# SparkFun_WiFly_GSX_Breakout.net
KiCad netlist of a schematic drawn in EAGLE
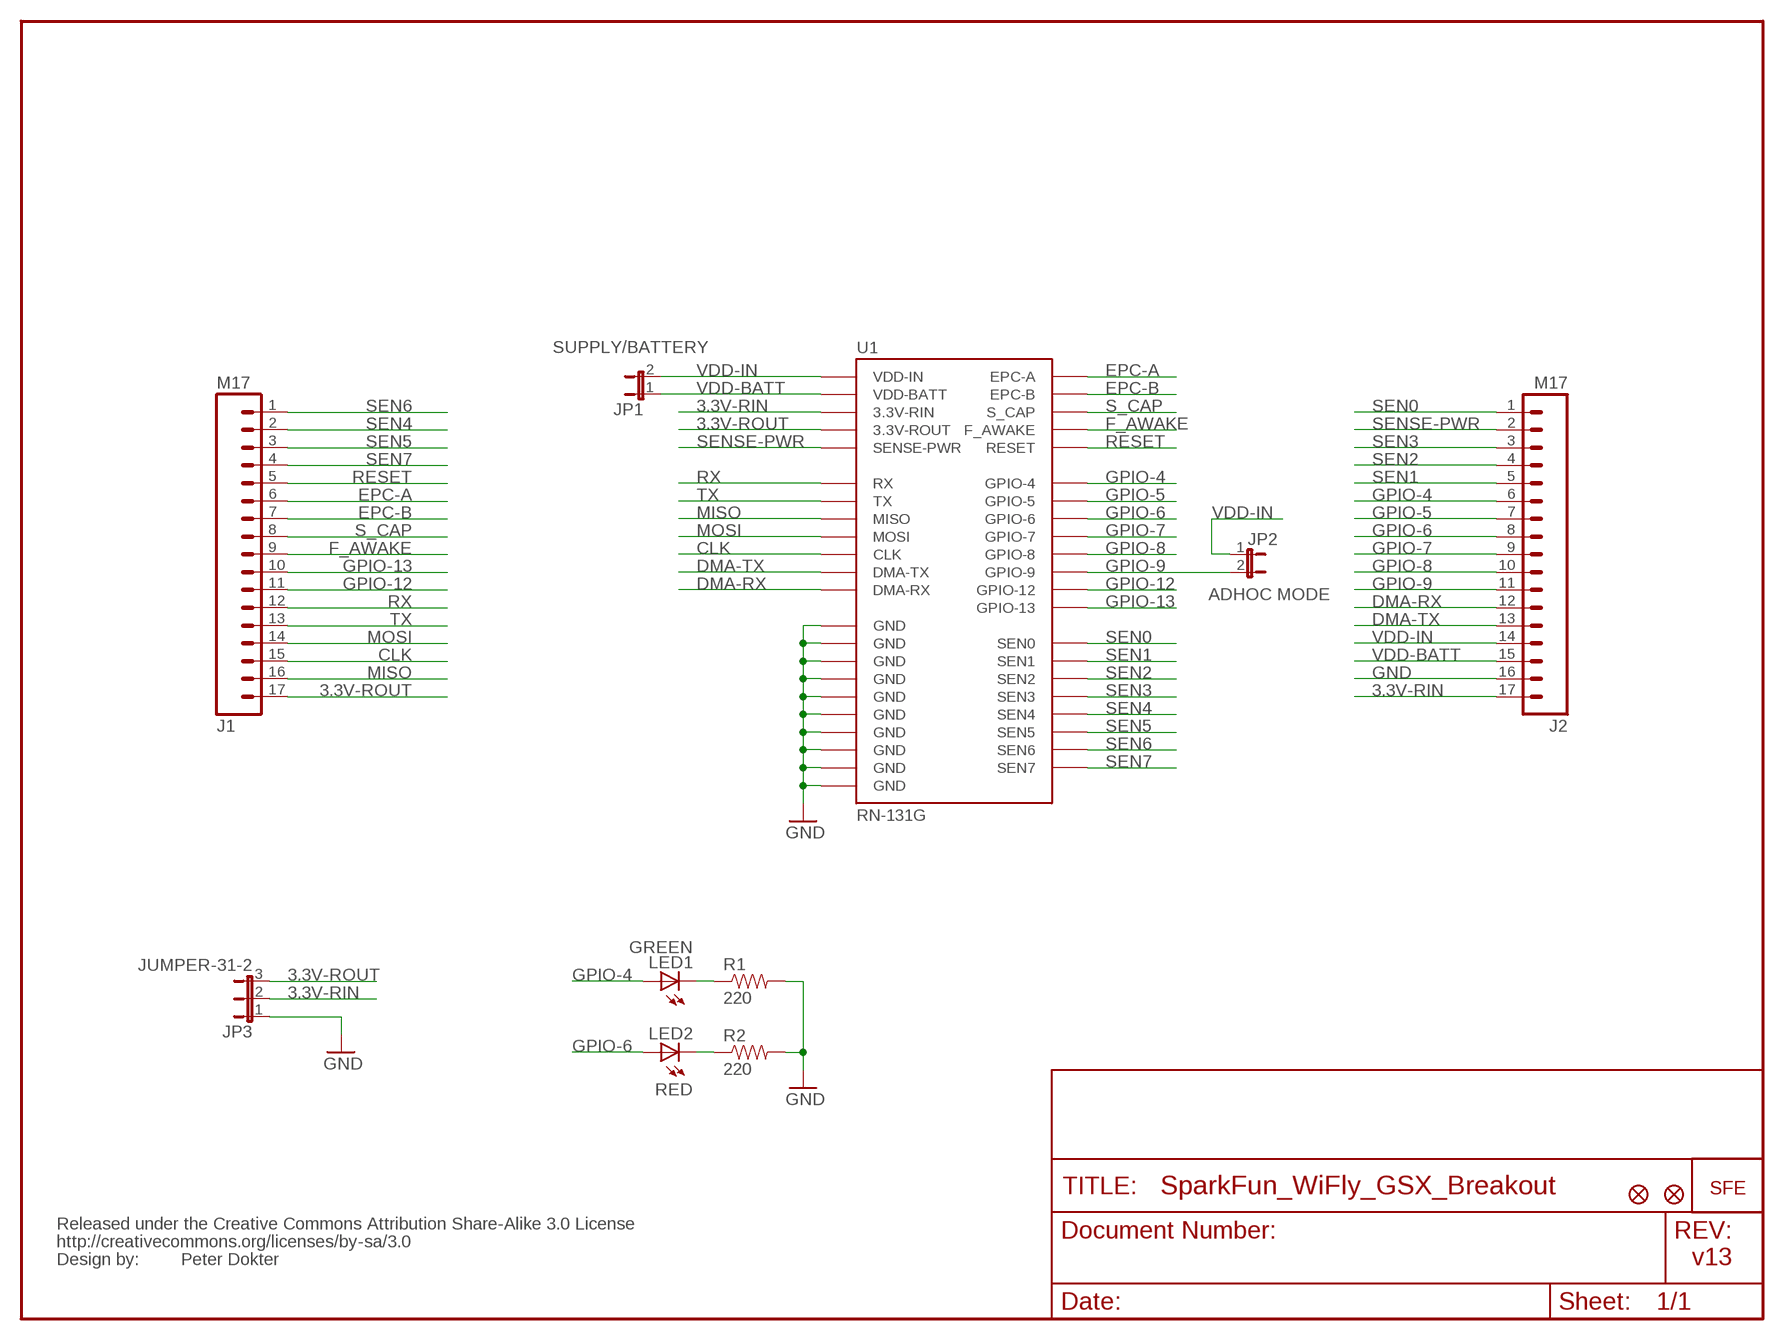
[diagram p0: schematic, sheet 1]

(export (version "E")
  (design (tool "Eeschema 10.0.6"))
  (components
    (comp (ref "J1")
      (value "M17")
      (footprint "eagle-import:1X17")
      (libsource (lib "eagle-import") (part "M17"))
    )
    (comp (ref "J2")
      (value "M17")
      (footprint "eagle-import:1X17")
      (libsource (lib "eagle-import") (part "M17"))
    )
    (comp (ref "JP1")
      (value "JUMPER-2SMD-NO")
      (footprint "eagle-import:SJ_2S-NO")
      (libsource (lib "eagle-import") (part "JUMPER-2SMD-NO"))
    )
    (comp (ref "JP2")
      (value "JUMPER-2SMD-NO")
      (footprint "eagle-import:SJ_2S-NO")
      (libsource (lib "eagle-import") (part "JUMPER-2SMD-NO"))
    )
    (comp (ref "JP3")
      (value "JUMPER-31-2")
      (footprint "eagle-import:SJ_3_PASTE1&2")
      (libsource (lib "eagle-import") (part "JUMPER-31-2"))
    )
    (comp (ref "LED1")
      (value "GREEN")
      (footprint "eagle-import:LED-0603")
      (libsource (lib "eagle-import") (part "LED0603"))
    )
    (comp (ref "LED2")
      (value "RED")
      (footprint "eagle-import:LED-0603")
      (libsource (lib "eagle-import") (part "LED0603"))
    )
    (comp (ref "R1")
      (value "220")
      (footprint "eagle-import:0402-RES")
      (libsource (lib "eagle-import") (part "RESISTOR0402-RES"))
    )
    (comp (ref "R2")
      (value "220")
      (footprint "eagle-import:0402-RES")
      (libsource (lib "eagle-import") (part "RESISTOR0402-RES"))
    )
    (comp (ref "U$1")
      (value "LOGO-SFENEW")
      (footprint "eagle-import:SFE-NEW-WEBLOGO")
      (libsource (lib "eagle-import") (part "LOGO-SFENEW"))
    )
    (comp (ref "U$2")
      (value "FIDUCIAL1X2")
      (footprint "eagle-import:FIDUCIAL-1X2")
      (libsource (lib "eagle-import") (part "FIDUCIAL1X2"))
    )
    (comp (ref "U$3")
      (value "FIDUCIAL1X2")
      (footprint "eagle-import:FIDUCIAL-1X2")
      (libsource (lib "eagle-import") (part "FIDUCIAL1X2"))
    )
    (comp (ref "U$4")
      (value "CREATIVE_COMMONS")
      (footprint "eagle-import:CREATIVE_COMMONS")
      (libsource (lib "eagle-import") (part "CREATIVE_COMMONS"))
    )
    (comp (ref "U1")
      (value "RN-131G")
      (footprint "eagle-import:RN-131G")
      (libsource (lib "eagle-import") (part "RN-131G"))
    )
  )
  (nets
    (net (code "1") (name "/3.3V-RIN") (class "Default")
      (node (ref "J2") (pin "17") (pinfunction "17_17") (pintype "passive"))
      (node (ref "JP3") (pin "2") (pinfunction "2_2") (pintype "passive"))
      (node (ref "U1") (pin "P$18") (pinfunction "3.3V-RIN_P$18") (pintype "bidirectional"))
    )
    (net (code "2") (name "/3.3V-ROUT") (class "Default")
      (node (ref "J1") (pin "17") (pinfunction "17_17") (pintype "passive"))
      (node (ref "JP3") (pin "3") (pinfunction "3_3") (pintype "passive"))
      (node (ref "U1") (pin "P$17") (pinfunction "3.3V-ROUT_P$17") (pintype "bidirectional"))
    )
    (net (code "3") (name "/CLK") (class "Default")
      (node (ref "J1") (pin "15") (pinfunction "15_15") (pintype "passive"))
      (node (ref "U1") (pin "P$15") (pinfunction "CLK_P$15") (pintype "bidirectional"))
    )
    (net (code "4") (name "/DMA-RX") (class "Default")
      (node (ref "J2") (pin "12") (pinfunction "12_12") (pintype "passive"))
      (node (ref "U1") (pin "P$23") (pinfunction "DMA-RX_P$23") (pintype "bidirectional"))
    )
    (net (code "5") (name "/DMA-TX") (class "Default")
      (node (ref "J2") (pin "13") (pinfunction "13_13") (pintype "passive"))
      (node (ref "U1") (pin "P$22") (pinfunction "DMA-TX_P$22") (pintype "bidirectional"))
    )
    (net (code "6") (name "/EPC-A") (class "Default")
      (node (ref "J1") (pin "6") (pinfunction "6_6") (pintype "passive"))
      (node (ref "U1") (pin "P$6") (pinfunction "EPC-A_P$6") (pintype "bidirectional"))
    )
    (net (code "7") (name "/EPC-B") (class "Default")
      (node (ref "J1") (pin "7") (pinfunction "7_7") (pintype "passive"))
      (node (ref "U1") (pin "P$7") (pinfunction "EPC-B_P$7") (pintype "bidirectional"))
    )
    (net (code "8") (name "/F_AWAKE") (class "Default")
      (node (ref "J1") (pin "9") (pinfunction "9_9") (pintype "passive"))
      (node (ref "U1") (pin "P$9") (pinfunction "F_AWAKE_P$9") (pintype "bidirectional"))
    )
    (net (code "9") (name "/GPIO-4") (class "Default")
      (node (ref "J2") (pin "6") (pinfunction "6_6") (pintype "passive"))
      (node (ref "LED1") (pin "A") (pinfunction "A_A") (pintype "passive"))
      (node (ref "U1") (pin "P$29") (pinfunction "GPIO-4_P$29") (pintype "bidirectional"))
    )
    (net (code "10") (name "/GPIO-5") (class "Default")
      (node (ref "J2") (pin "7") (pinfunction "7_7") (pintype "passive"))
      (node (ref "U1") (pin "P$28") (pinfunction "GPIO-5_P$28") (pintype "bidirectional"))
    )
    (net (code "11") (name "/GPIO-6") (class "Default")
      (node (ref "J2") (pin "8") (pinfunction "8_8") (pintype "passive"))
      (node (ref "LED2") (pin "A") (pinfunction "A_A") (pintype "passive"))
      (node (ref "U1") (pin "P$27") (pinfunction "GPIO-6_P$27") (pintype "bidirectional"))
    )
    (net (code "12") (name "/GPIO-7") (class "Default")
      (node (ref "J2") (pin "9") (pinfunction "9_9") (pintype "passive"))
      (node (ref "U1") (pin "P$26") (pinfunction "GPIO-7_P$26") (pintype "bidirectional"))
    )
    (net (code "13") (name "/GPIO-8") (class "Default")
      (node (ref "J2") (pin "10") (pinfunction "10_10") (pintype "passive"))
      (node (ref "U1") (pin "P$25") (pinfunction "GPIO-8_P$25") (pintype "bidirectional"))
    )
    (net (code "14") (name "/GPIO-9") (class "Default")
      (node (ref "J2") (pin "11") (pinfunction "11_11") (pintype "passive"))
      (node (ref "JP2") (pin "2") (pinfunction "2_2") (pintype "passive"))
      (node (ref "U1") (pin "P$24") (pinfunction "GPIO-9_P$24") (pintype "bidirectional"))
    )
    (net (code "15") (name "/GPIO-12") (class "Default")
      (node (ref "J1") (pin "11") (pinfunction "11_11") (pintype "passive"))
      (node (ref "U1") (pin "P$11") (pinfunction "GPIO-12_P$11") (pintype "bidirectional"))
    )
    (net (code "16") (name "/GPIO-13") (class "Default")
      (node (ref "J1") (pin "10") (pinfunction "10_10") (pintype "passive"))
      (node (ref "U1") (pin "P$10") (pinfunction "GPIO-13_P$10") (pintype "bidirectional"))
    )
    (net (code "17") (name "/MISO") (class "Default")
      (node (ref "J1") (pin "16") (pinfunction "16_16") (pintype "passive"))
      (node (ref "U1") (pin "P$16") (pinfunction "MISO_P$16") (pintype "bidirectional"))
    )
    (net (code "18") (name "/MOSI") (class "Default")
      (node (ref "J1") (pin "14") (pinfunction "14_14") (pintype "passive"))
      (node (ref "U1") (pin "P$14") (pinfunction "MOSI_P$14") (pintype "bidirectional"))
    )
    (net (code "19") (name "/RESET") (class "Default")
      (node (ref "J1") (pin "5") (pinfunction "5_5") (pintype "passive"))
      (node (ref "U1") (pin "P$5") (pinfunction "RESET_P$5") (pintype "bidirectional"))
    )
    (net (code "20") (name "/RX") (class "Default")
      (node (ref "J1") (pin "12") (pinfunction "12_12") (pintype "passive"))
      (node (ref "U1") (pin "P$12") (pinfunction "RX_P$12") (pintype "bidirectional"))
    )
    (net (code "21") (name "/SEN0") (class "Default")
      (node (ref "J2") (pin "1") (pinfunction "1_1") (pintype "passive"))
      (node (ref "U1") (pin "P$34") (pinfunction "SEN0_P$34") (pintype "bidirectional"))
    )
    (net (code "22") (name "/SEN1") (class "Default")
      (node (ref "J2") (pin "5") (pinfunction "5_5") (pintype "passive"))
      (node (ref "U1") (pin "P$30") (pinfunction "SEN1_P$30") (pintype "bidirectional"))
    )
    (net (code "23") (name "/SEN2") (class "Default")
      (node (ref "J2") (pin "4") (pinfunction "4_4") (pintype "passive"))
      (node (ref "U1") (pin "P$31") (pinfunction "SEN2_P$31") (pintype "bidirectional"))
    )
    (net (code "24") (name "/SEN3") (class "Default")
      (node (ref "J2") (pin "3") (pinfunction "3_3") (pintype "passive"))
      (node (ref "U1") (pin "P$32") (pinfunction "SEN3_P$32") (pintype "bidirectional"))
    )
    (net (code "25") (name "/SEN4") (class "Default")
      (node (ref "J1") (pin "2") (pinfunction "2_2") (pintype "passive"))
      (node (ref "U1") (pin "P$2") (pinfunction "SEN4_P$2") (pintype "bidirectional"))
    )
    (net (code "26") (name "/SEN5") (class "Default")
      (node (ref "J1") (pin "3") (pinfunction "3_3") (pintype "passive"))
      (node (ref "U1") (pin "P$3") (pinfunction "SEN5_P$3") (pintype "bidirectional"))
    )
    (net (code "27") (name "/SEN6") (class "Default")
      (node (ref "J1") (pin "1") (pinfunction "1_1") (pintype "passive"))
      (node (ref "U1") (pin "P$1") (pinfunction "SEN6_P$1") (pintype "bidirectional"))
    )
    (net (code "28") (name "/SEN7") (class "Default")
      (node (ref "J1") (pin "4") (pinfunction "4_4") (pintype "passive"))
      (node (ref "U1") (pin "P$4") (pinfunction "SEN7_P$4") (pintype "bidirectional"))
    )
    (net (code "29") (name "/SENSE-PWR") (class "Default")
      (node (ref "J2") (pin "2") (pinfunction "2_2") (pintype "passive"))
      (node (ref "U1") (pin "P$33") (pinfunction "SENSE-PWR_P$33") (pintype "bidirectional"))
    )
    (net (code "30") (name "/S_CAP") (class "Default")
      (node (ref "J1") (pin "8") (pinfunction "8_8") (pintype "passive"))
      (node (ref "U1") (pin "P$8") (pinfunction "S_CAP_P$8") (pintype "bidirectional"))
    )
    (net (code "31") (name "/TX") (class "Default")
      (node (ref "J1") (pin "13") (pinfunction "13_13") (pintype "passive"))
      (node (ref "U1") (pin "P$13") (pinfunction "TX_P$13") (pintype "bidirectional"))
    )
    (net (code "32") (name "/VDD-BATT") (class "Default")
      (node (ref "J2") (pin "15") (pinfunction "15_15") (pintype "passive"))
      (node (ref "JP1") (pin "1") (pinfunction "1_1") (pintype "passive"))
      (node (ref "U1") (pin "P$20") (pinfunction "VDD-BATT_P$20") (pintype "bidirectional"))
    )
    (net (code "33") (name "/VDD-IN") (class "Default")
      (node (ref "J2") (pin "14") (pinfunction "14_14") (pintype "passive"))
      (node (ref "JP1") (pin "2") (pinfunction "2_2") (pintype "passive"))
      (node (ref "JP2") (pin "1") (pinfunction "1_1") (pintype "passive"))
      (node (ref "U1") (pin "P$21") (pinfunction "VDD-IN_P$21") (pintype "bidirectional"))
    )
    (net (code "34") (name "GND") (class "Default")
      (node (ref "J2") (pin "16") (pinfunction "16_16") (pintype "passive"))
      (node (ref "JP3") (pin "1") (pinfunction "1_1") (pintype "passive"))
      (node (ref "R1") (pin "2") (pinfunction "2_2") (pintype "passive"))
      (node (ref "R2") (pin "2") (pinfunction "2_2") (pintype "passive"))
      (node (ref "U1") (pin "P$19") (pinfunction "GND_P$19") (pintype "bidirectional"))
      (node (ref "U1") (pin "P$36") (pinfunction "GND_P$36") (pintype "bidirectional"))
      (node (ref "U1") (pin "P$37") (pinfunction "GND_P$37") (pintype "bidirectional"))
      (node (ref "U1") (pin "P$38") (pinfunction "GND_P$38") (pintype "bidirectional"))
      (node (ref "U1") (pin "P$39") (pinfunction "GND_P$39") (pintype "bidirectional"))
      (node (ref "U1") (pin "P$40") (pinfunction "GND_P$40") (pintype "bidirectional"))
      (node (ref "U1") (pin "P$41") (pinfunction "GND_P$41") (pintype "bidirectional"))
      (node (ref "U1") (pin "P$42") (pinfunction "GND_P$42") (pintype "bidirectional"))
      (node (ref "U1") (pin "P$43") (pinfunction "GND_P$43") (pintype "bidirectional"))
      (node (ref "U1") (pin "P$44") (pinfunction "GND_P$44") (pintype "bidirectional"))
    )
    (net (code "35") (name "Net-(LED1-PadC)") (class "Default")
      (node (ref "LED1") (pin "C") (pinfunction "C_C") (pintype "passive"))
      (node (ref "R1") (pin "1") (pinfunction "1_1") (pintype "passive"))
    )
    (net (code "36") (name "Net-(LED2-PadC)") (class "Default")
      (node (ref "LED2") (pin "C") (pinfunction "C_C") (pintype "passive"))
      (node (ref "R2") (pin "1") (pinfunction "1_1") (pintype "passive"))
    )
  )
)
